# SAM4N_Xplained_Pro_Oscillators.net
KiCad netlist of a schematic drawn in Altium Designer
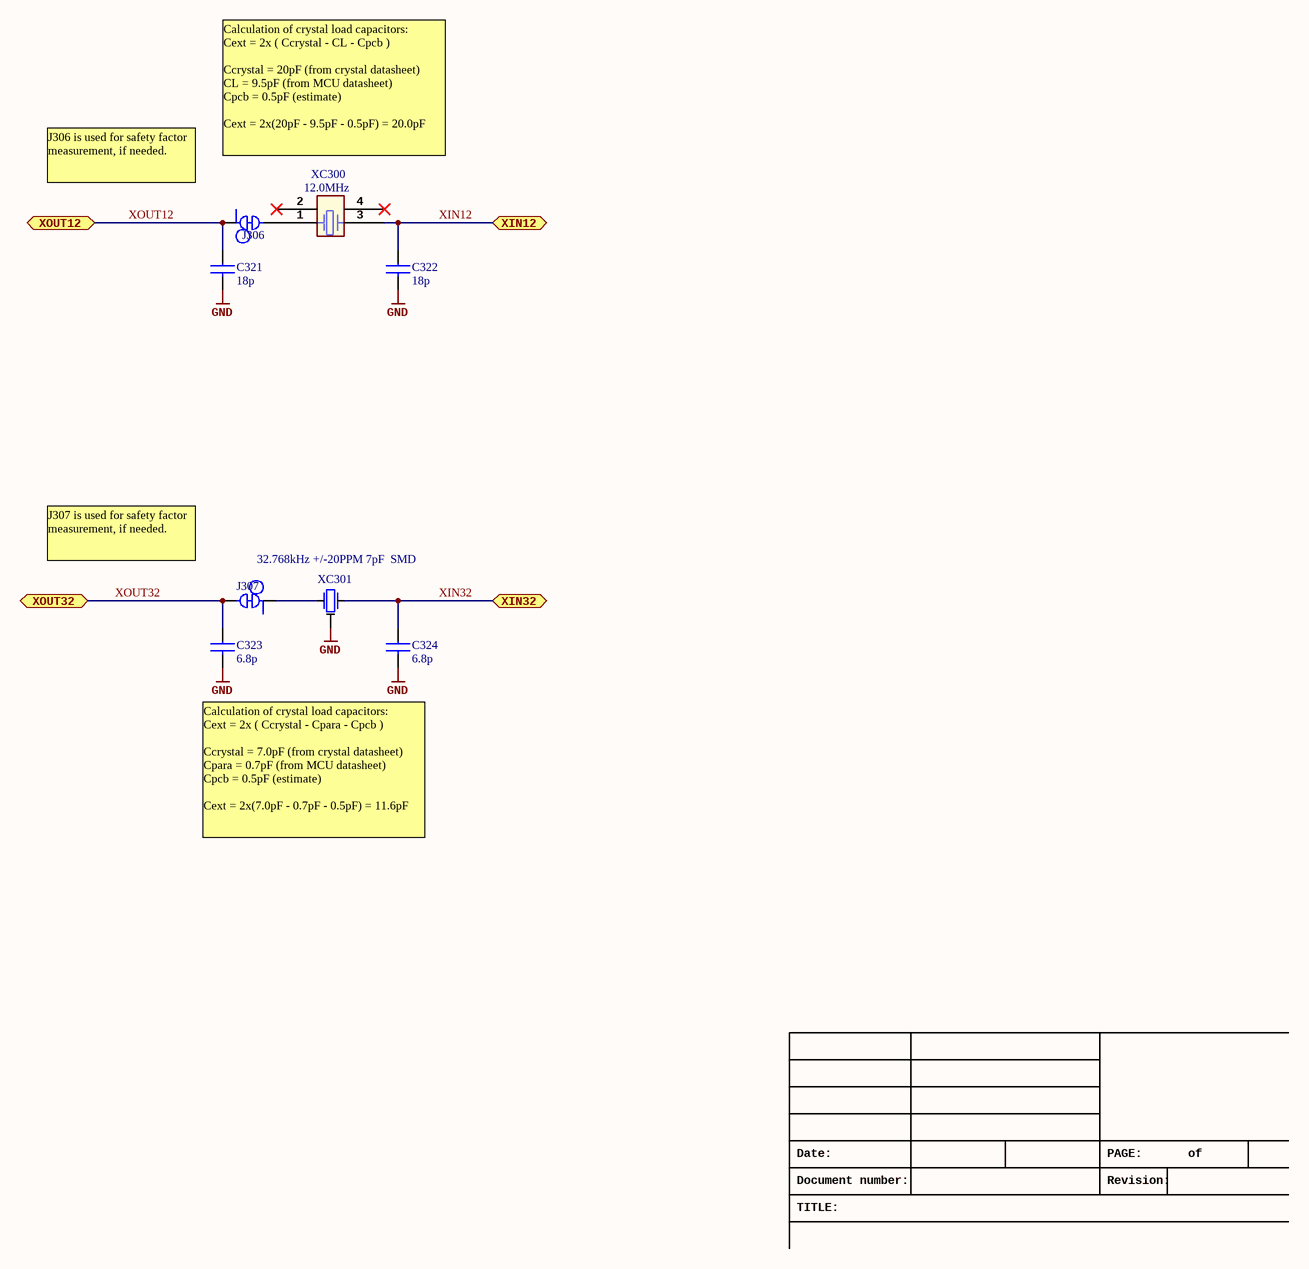
[diagram p0: SAM4N_Xplained_Pro_Oscillators.SchDoc]

(export (version "E")
  (design (tool "Eeschema 10.0.6"))
  (components
    (comp (ref "C321")
      (value "18p")
      (footprint "AP1-00001")
      (description "Ceramic capacitor, SMD 0402, NP0, 50V, +/-5%")
      (fields (field (name "TOLERANCE") "50V, +/-5%") (field (name "VERIFIED BY") "Lars Helge Mo"))
      (libsource (lib "AltiumDbLib") (part "CAP-NONPOL"))
    )
    (comp (ref "C322")
      (value "18p")
      (footprint "AP1-00001")
      (description "Ceramic capacitor, SMD 0402, NP0, 50V, +/-5%")
      (fields (field (name "TOLERANCE") "50V, +/-5%") (field (name "VERIFIED BY") "Lars Helge Mo"))
      (libsource (lib "AltiumDbLib") (part "CAP-NONPOL"))
    )
    (comp (ref "C323")
      (value "6.8p")
      (footprint "AP1-00001")
      (description "Ceramic capacitor, SMD 0402, NP0, 50V, +/-5%")
      (fields
        (field (name "TOLERANCE") "50V, +/-5%")
        (field (name "Comment") "CAP-NONPOL")
        (field (name "VERIFIED BY") "Lars Helge Mo")
      )
      (libsource (lib "AltiumDbLib") (part "CAP-NONPOL"))
    )
    (comp (ref "C324")
      (value "6.8p")
      (footprint "AP1-00001")
      (description "Ceramic capacitor, SMD 0402, NP0, 50V, +/-5%")
      (fields
        (field (name "TOLERANCE") "50V, +/-5%")
        (field (name "Comment") "CAP-NONPOL")
        (field (name "VERIFIED BY") "Lars Helge Mo")
      )
      (libsource (lib "AltiumDbLib") (part "CAP-NONPOL"))
    )
    (comp (ref "J306")
      (value "SMD-STRAP_CLOSED")
      (footprint "AP9-00044")
      (description "Default closed SMD strap, 0603 size")
      (libsource (lib "AltiumDbLib") (part "SMD-STRAP_CLOSED"))
    )
    (comp (ref "J307")
      (value "SMD-STRAP_CLOSED")
      (footprint "AP9-00044")
      (description "Default closed SMD strap, 0603 size")
      (libsource (lib "AltiumDbLib") (part "SMD-STRAP_CLOSED"))
    )
    (comp (ref "XC300")
      (value "12.0MHz")
      (footprint "AP7-00039")
      (description "Fox FQ5032B 12.0MHz SMD crystal 738B-12")
      (fields
        (field (name "TOLERANCE") "30PPM")
        (field (name "MANUFACTURER") "Fox  Electronics")
        (field (name "VERIFIED BY") "Ketil Skjerve")
      )
      (libsource (lib "AltiumDbLib") (part "CRYSTAL1324"))
    )
    (comp (ref "XC301")
      (value "32.768kHz +/-20PPM 7pF  SMD")
      (footprint "AP7-00044")
      (description "32k768 crystal, +-20ppm, CL=7pF, max ESR 60kOhm, SMD")
      (fields (field (name "TOLERANCE") "+/- 20 PPM") (field (name "MANUFACTURER") "Micro Crystal"))
      (libsource (lib "AltiumDbLib") (part "CRYSTAL_2P_metal"))
    )
  )
  (nets
    (net (code "1") (name "/XIN12") (class "Default")
      (node (ref "C322") (pin "1") (pinfunction "1_1") (pintype "passive"))
      (node (ref "XC300") (pin "3") (pinfunction "3_3") (pintype "passive"))
    )
    (net (code "2") (name "/XIN32") (class "Default")
      (node (ref "C324") (pin "1") (pinfunction "1_1") (pintype "passive"))
      (node (ref "XC301") (pin "2") (pinfunction "2_2") (pintype "passive"))
    )
    (net (code "3") (name "/XOUT12") (class "Default")
      (node (ref "C321") (pin "1") (pinfunction "1_1") (pintype "passive"))
      (node (ref "J306") (pin "1") (pinfunction "1_1") (pintype "passive"))
    )
    (net (code "4") (name "/XOUT32") (class "Default")
      (node (ref "C323") (pin "1") (pinfunction "1_1") (pintype "passive"))
      (node (ref "J307") (pin "2") (pinfunction "2_2") (pintype "passive"))
    )
    (net (code "5") (name "GND") (class "Default")
      (node (ref "C321") (pin "2") (pinfunction "2_2") (pintype "passive"))
      (node (ref "C322") (pin "2") (pinfunction "2_2") (pintype "passive"))
      (node (ref "C323") (pin "2") (pinfunction "2_2") (pintype "passive"))
      (node (ref "C324") (pin "2") (pinfunction "2_2") (pintype "passive"))
      (node (ref "XC301") (pin "3") (pinfunction "3_3") (pintype "passive"))
    )
    (net (code "6") (name "Net-(J306-Pad2)") (class "Default")
      (node (ref "J306") (pin "2") (pinfunction "2_2") (pintype "passive"))
      (node (ref "XC300") (pin "1") (pinfunction "1_1") (pintype "passive"))
    )
    (net (code "7") (name "Net-(J307-Pad1)") (class "Default")
      (node (ref "J307") (pin "1") (pinfunction "1_1") (pintype "passive"))
      (node (ref "XC301") (pin "1") (pinfunction "1_1") (pintype "passive"))
    )
    (net (code "8") (name "unconnected-(XC300-Pad2)") (class "Default")
      (node (ref "XC300") (pin "2") (pinfunction "2_2") (pintype "passive+no_connect"))
    )
    (net (code "9") (name "unconnected-(XC300-Pad4)") (class "Default")
      (node (ref "XC300") (pin "4") (pinfunction "4_4") (pintype "passive+no_connect"))
    )
  )
)
